# SDCARD.net
KiCad netlist of a schematic drawn in Altium Designer
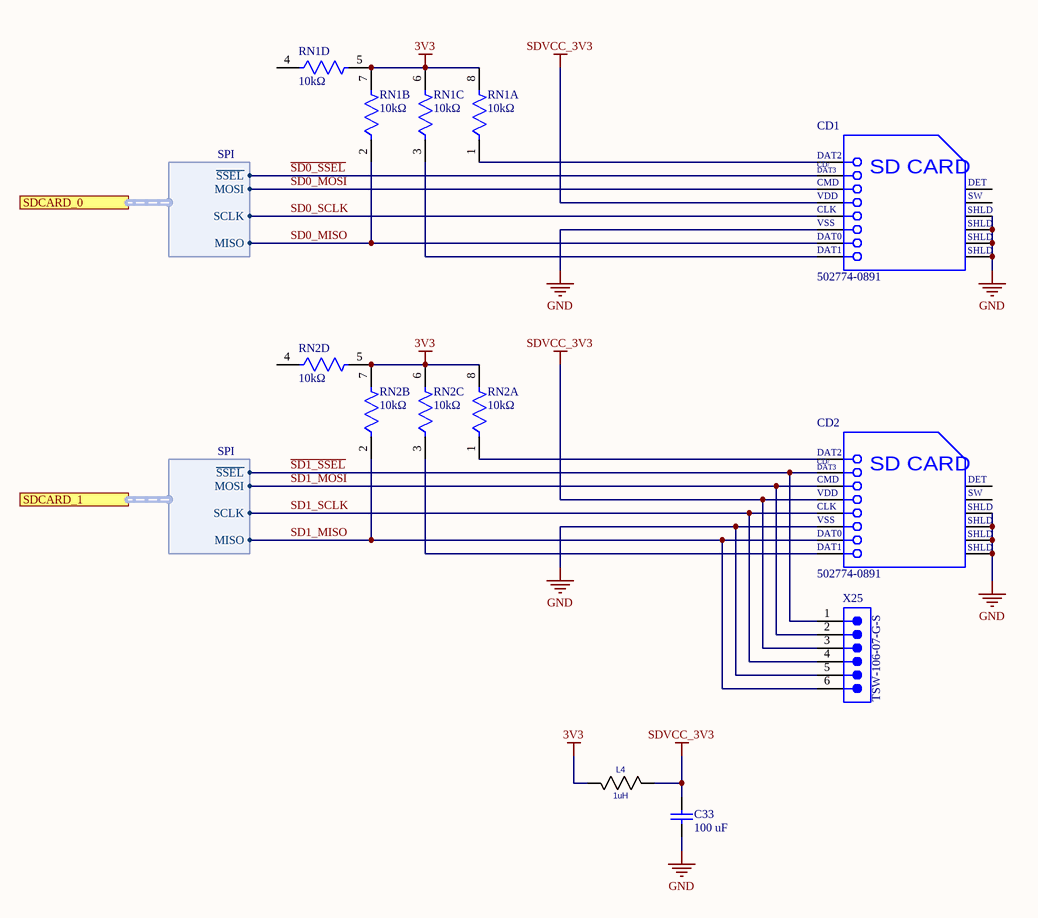
[diagram p0: SDCARD.SchDoc]

(export (version "E")
  (design (tool "Eeschema 10.0.6"))
  (components
    (comp (ref "C33")
      (value "GRM31CR60J107ME39L")
      (footprint "CAPC3216X190X55ML30T25")
      (description "Chip Capacitor, 100 uF, +/- 20%, 6.3 V, -55 to 85 degC, 1206 (3216 Metric), RoHS, Tape and Reel")
      (fields (field (name "CAPACITANCE") "100 uF") (field (name "MANUFACTURER") "Murata"))
      (libsource (lib "SchLib") (part "CMP-1662-00011-2"))
    )
    (comp (ref "CD1")
      (value "502774-0891")
      (footprint "MOLX-502774-0891_V")
      (description "Micro SD Memory Card Connector, 0.5 A, 10 V (DC), -25 to 85 degC, 8-Pin SMT, RoHS, Tape and Reel")
      (fields (field (name "MANUFACTURER") "Molex") (field (name "MANUFACTURER PART NUMBER") "5027740891"))
      (libsource (lib "SchLib") (part "CMP-2000-05248-1"))
    )
    (comp (ref "CD2")
      (value "502774-0891")
      (footprint "MOLX-502774-0891_V")
      (description "Micro SD Memory Card Connector, 0.5 A, 10 V (DC), -25 to 85 degC, 8-Pin SMT, RoHS, Tape and Reel")
      (fields (field (name "MANUFACTURER") "Molex") (field (name "MANUFACTURER PART NUMBER") "5027740891"))
      (libsource (lib "SchLib") (part "CMP-2000-05248-1"))
    )
    (comp (ref "L4")
      (value "1uH")
      (footprint "L-CHIP")
      (description "L-CHIP")
      (libsource (lib "SchLib") (part "L-CHIP"))
    )
    (comp (ref "RN1")
      (value "CAT16-1002F4LF")
      (footprint "FP-CAT16-F4-MFG")
      (description "RES ARRAY 4 RES 10K OHM 1206")
      (fields
        (field (name "RESISTANCE") "10kΩ")
        (field (name "TOLERANCE") "1%")
        (field (name "OCTOPART") "https://octopart.com/cat16-1002f4lf-bourns-1624551")
      )
      (libsource (lib "Altium Content Vault") (part "46c0e806a6f3a765a2d55930d12d044"))
    )
    (comp (ref "RN2")
      (value "CAT16-1002F4LF")
      (footprint "FP-CAT16-F4-MFG")
      (description "RES ARRAY 4 RES 10K OHM 1206")
      (fields
        (field (name "RESISTANCE") "10kΩ")
        (field (name "TOLERANCE") "1%")
        (field (name "OCTOPART") "https://octopart.com/cat16-1002f4lf-bourns-1624551")
      )
      (libsource (lib "Altium Content Vault") (part "46c0e806a6f3a765a2d55930d12d044"))
    )
    (comp (ref "X25")
      (value "TSW-106-07-G-S")
      (footprint "SMTC-TSW-106-07-X-S")
      (description "0.025\" SQ Post Header, Through-hole, Vertical, -55 to 125 degC, 2.54 mm Pitch, 6-Pin, Male, RoHS")
      (fields (field (name "MANUFACTURER") "Samtec"))
      (libsource (lib "SchLib") (part "CMP-1024-00383-1"))
    )
  )
  (nets
    (net (code "2") (name "/SD0_MISO") (class "Default")
      (node (ref "CD1") (pin "7") (pinfunction "DAT0_7") (pintype "passive"))
      (node (ref "RN1") (pin "2") (pinfunction "2_2") (pintype "passive"))
    )
    (net (code "3") (name "/SD0_MOSI") (class "Default")
      (node (ref "CD1") (pin "3") (pinfunction "CMD_3") (pintype "passive"))
    )
    (net (code "4") (name "/SD0_SCLK") (class "Default")
      (node (ref "CD1") (pin "5") (pinfunction "CLK_5") (pintype "passive"))
    )
    (net (code "5") (name "/SD1_MISO") (class "Default")
      (node (ref "CD2") (pin "7") (pinfunction "DAT0_7") (pintype "passive"))
      (node (ref "RN2") (pin "2") (pinfunction "2_2") (pintype "passive"))
      (node (ref "X25") (pin "6") (pinfunction "6_6") (pintype "passive"))
    )
    (net (code "6") (name "/SD1_MOSI") (class "Default")
      (node (ref "CD2") (pin "3") (pinfunction "CMD_3") (pintype "passive"))
      (node (ref "X25") (pin "2") (pinfunction "2_2") (pintype "passive"))
    )
    (net (code "7") (name "/SD1_SCLK") (class "Default")
      (node (ref "CD2") (pin "5") (pinfunction "CLK_5") (pintype "passive"))
      (node (ref "X25") (pin "4") (pinfunction "4_4") (pintype "passive"))
    )
    (net (code "9") (name "/~{SD0_SSEL}") (class "Default")
      (node (ref "CD1") (pin "2") (pinfunction "CD/DAT3_2") (pintype "passive"))
    )
    (net (code "10") (name "/~{SD1_SSEL}") (class "Default")
      (node (ref "CD2") (pin "2") (pinfunction "CD/DAT3_2") (pintype "passive"))
      (node (ref "X25") (pin "1") (pinfunction "1_1") (pintype "passive"))
    )
    (net (code "11") (name "3V3") (class "Default")
      (node (ref "L4") (pin "2") (pintype "passive"))
      (node (ref "RN1") (pin "5") (pinfunction "5_5") (pintype "passive"))
      (node (ref "RN1") (pin "6") (pinfunction "6_6") (pintype "passive"))
      (node (ref "RN1") (pin "7") (pinfunction "7_7") (pintype "passive"))
      (node (ref "RN1") (pin "8") (pinfunction "8_8") (pintype "passive"))
      (node (ref "RN2") (pin "5") (pinfunction "5_5") (pintype "passive"))
      (node (ref "RN2") (pin "6") (pinfunction "6_6") (pintype "passive"))
      (node (ref "RN2") (pin "7") (pinfunction "7_7") (pintype "passive"))
      (node (ref "RN2") (pin "8") (pinfunction "8_8") (pintype "passive"))
    )
    (net (code "12") (name "GND") (class "Default")
      (node (ref "C33") (pin "1") (pinfunction "1_1") (pintype "passive"))
      (node (ref "CD1") (pin "11") (pinfunction "SHLD_11") (pintype "passive"))
      (node (ref "CD1") (pin "12") (pinfunction "SHLD_12") (pintype "passive"))
      (node (ref "CD1") (pin "13") (pinfunction "SHLD_13") (pintype "passive"))
      (node (ref "CD1") (pin "14") (pinfunction "SHLD_14") (pintype "passive"))
      (node (ref "CD1") (pin "6") (pinfunction "VSS_6") (pintype "passive"))
      (node (ref "CD2") (pin "11") (pinfunction "SHLD_11") (pintype "passive"))
      (node (ref "CD2") (pin "12") (pinfunction "SHLD_12") (pintype "passive"))
      (node (ref "CD2") (pin "13") (pinfunction "SHLD_13") (pintype "passive"))
      (node (ref "CD2") (pin "14") (pinfunction "SHLD_14") (pintype "passive"))
      (node (ref "CD2") (pin "6") (pinfunction "VSS_6") (pintype "passive"))
      (node (ref "X25") (pin "5") (pinfunction "5_5") (pintype "passive"))
    )
    (net (code "13") (name "Net-(CD1-DAT1)") (class "Default")
      (node (ref "CD1") (pin "8") (pinfunction "DAT1_8") (pintype "passive"))
      (node (ref "RN1") (pin "3") (pinfunction "3_3") (pintype "passive"))
    )
    (net (code "14") (name "Net-(CD1-DAT2)") (class "Default")
      (node (ref "CD1") (pin "1") (pinfunction "DAT2_1") (pintype "passive"))
      (node (ref "RN1") (pin "1") (pinfunction "1_1") (pintype "passive"))
    )
    (net (code "15") (name "Net-(CD2-DAT1)") (class "Default")
      (node (ref "CD2") (pin "8") (pinfunction "DAT1_8") (pintype "passive"))
      (node (ref "RN2") (pin "3") (pinfunction "3_3") (pintype "passive"))
    )
    (net (code "16") (name "Net-(CD2-DAT2)") (class "Default")
      (node (ref "CD2") (pin "1") (pinfunction "DAT2_1") (pintype "passive"))
      (node (ref "RN2") (pin "1") (pinfunction "1_1") (pintype "passive"))
    )
    (net (code "17") (name "SDVCC_3V3") (class "Default")
      (node (ref "C33") (pin "2") (pinfunction "2_2") (pintype "passive"))
      (node (ref "CD1") (pin "4") (pinfunction "VDD_4") (pintype "passive"))
      (node (ref "CD2") (pin "4") (pinfunction "VDD_4") (pintype "passive"))
      (node (ref "L4") (pin "1") (pintype "passive"))
      (node (ref "X25") (pin "3") (pinfunction "3_3") (pintype "passive"))
    )
    (net (code "18") (name "unconnected-(CD1-DETECT-Pad9)") (class "Default")
      (node (ref "CD1") (pin "9") (pinfunction "DETECT_9") (pintype "passive"))
    )
    (net (code "19") (name "unconnected-(CD1-SWITCH-Pad10)") (class "Default")
      (node (ref "CD1") (pin "10") (pinfunction "SWITCH_10") (pintype "passive"))
    )
    (net (code "20") (name "unconnected-(CD2-DETECT-Pad9)") (class "Default")
      (node (ref "CD2") (pin "9") (pinfunction "DETECT_9") (pintype "passive"))
    )
    (net (code "21") (name "unconnected-(CD2-SWITCH-Pad10)") (class "Default")
      (node (ref "CD2") (pin "10") (pinfunction "SWITCH_10") (pintype "passive"))
    )
    (net (code "22") (name "unconnected-(RN1-Pad4)") (class "Default")
      (node (ref "RN1") (pin "4") (pinfunction "4_4") (pintype "passive"))
    )
    (net (code "23") (name "unconnected-(RN2-Pad4)") (class "Default")
      (node (ref "RN2") (pin "4") (pinfunction "4_4") (pintype "passive"))
    )
  )
)
